# GFB_Basisstation.net
KiCad netlist of a schematic drawn in EAGLE
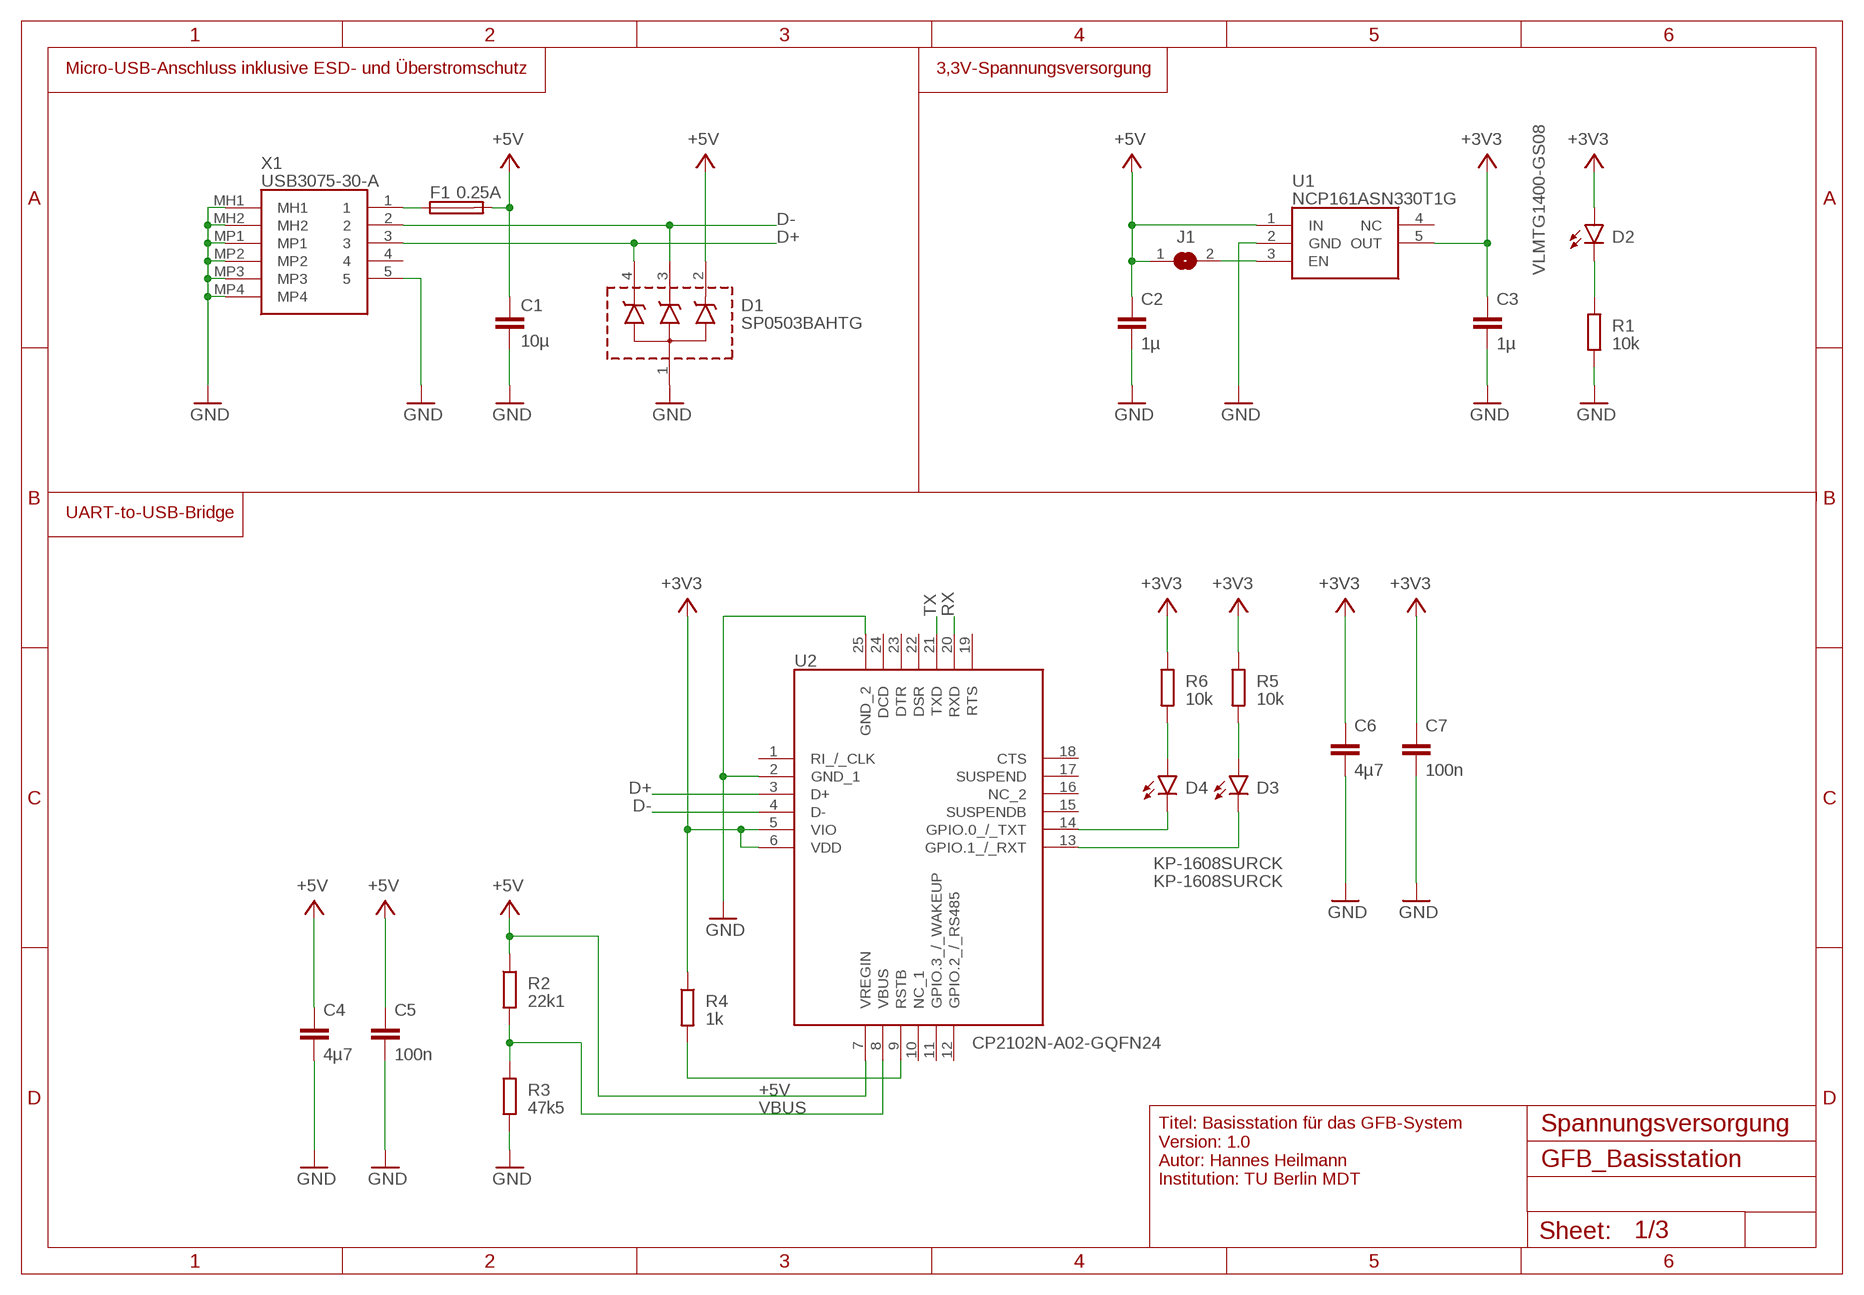
[diagram p0: schematic, sheet 1]
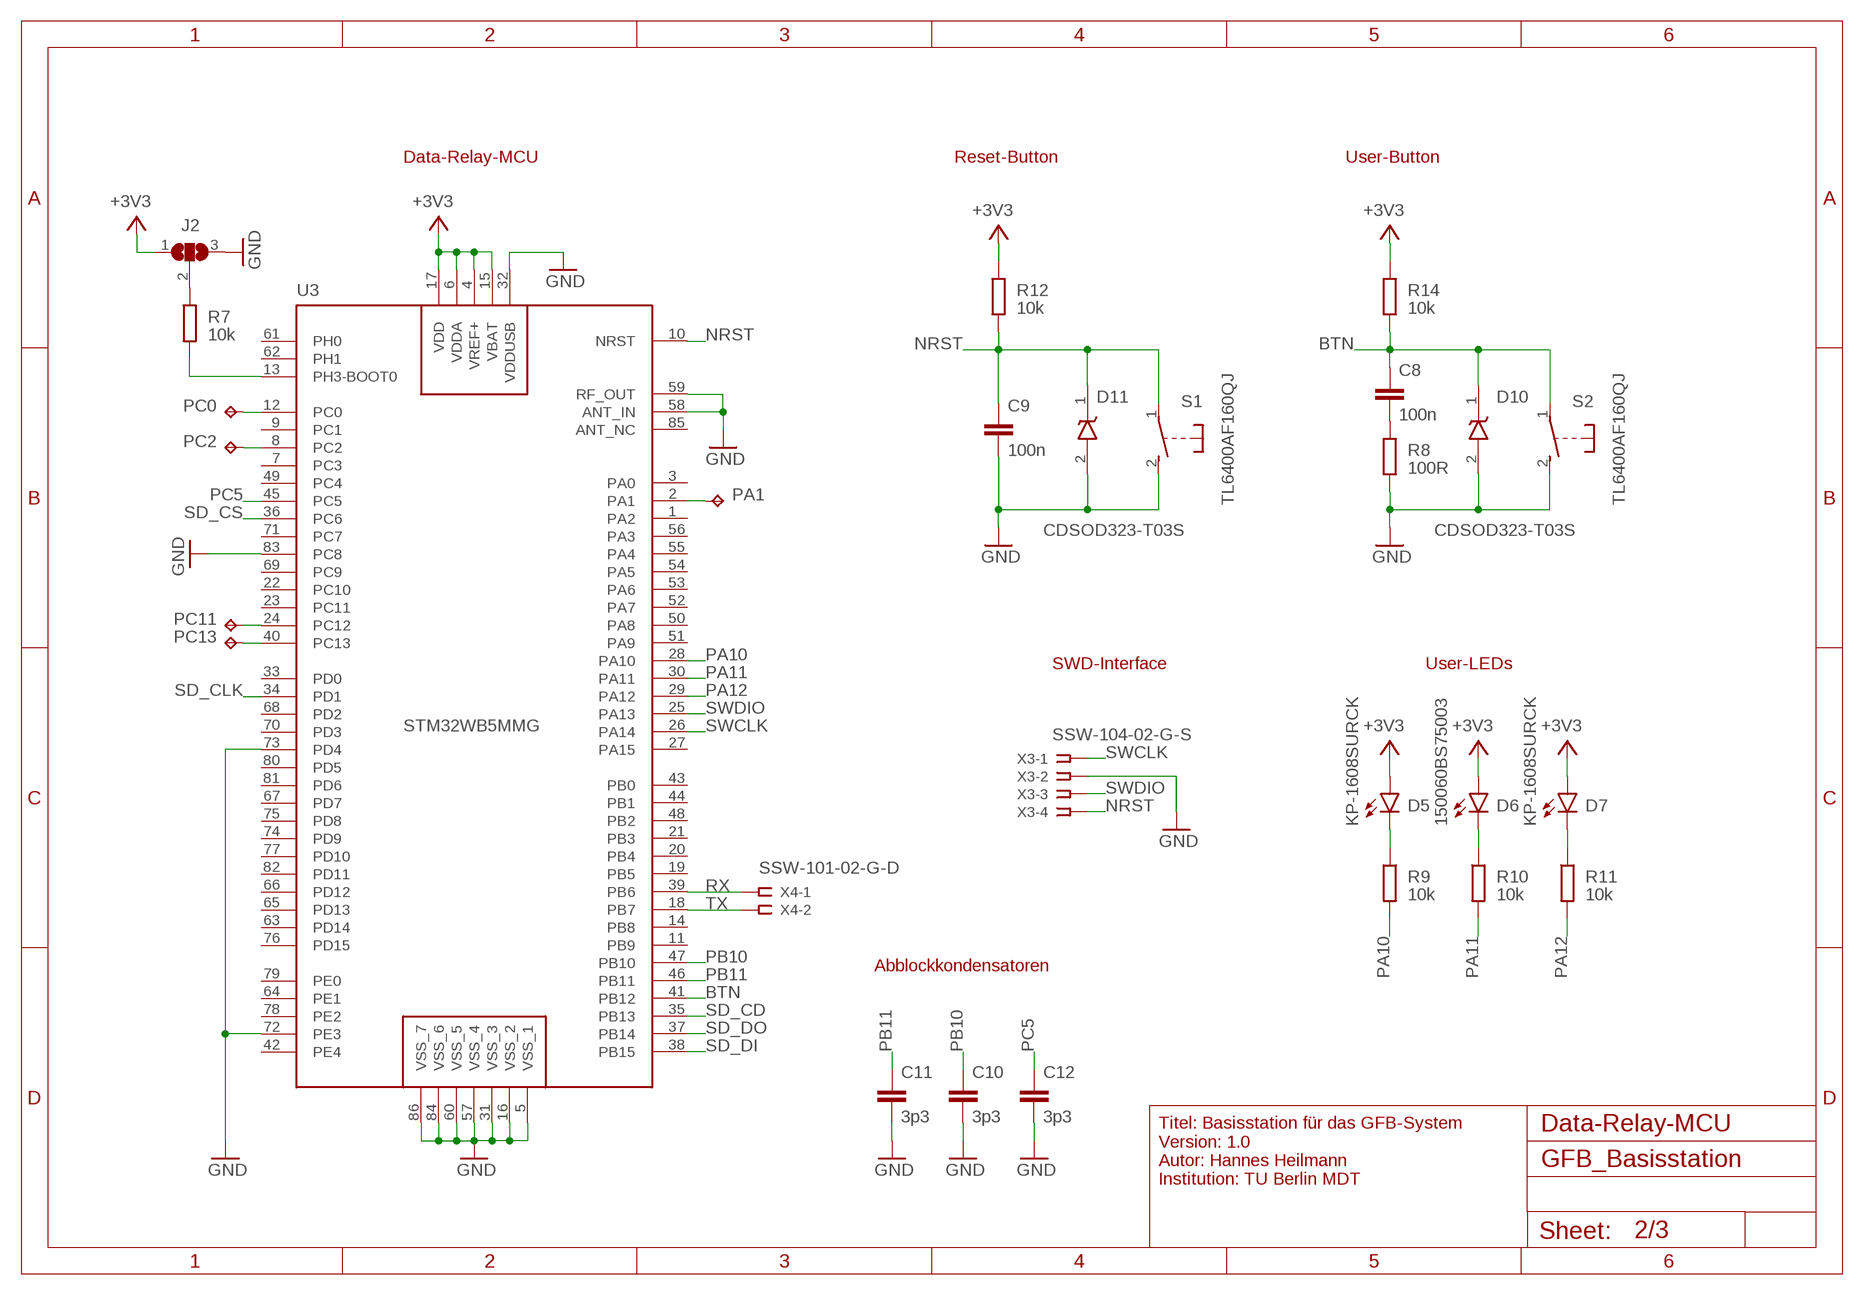
[diagram p1: schematic, sheet 2]
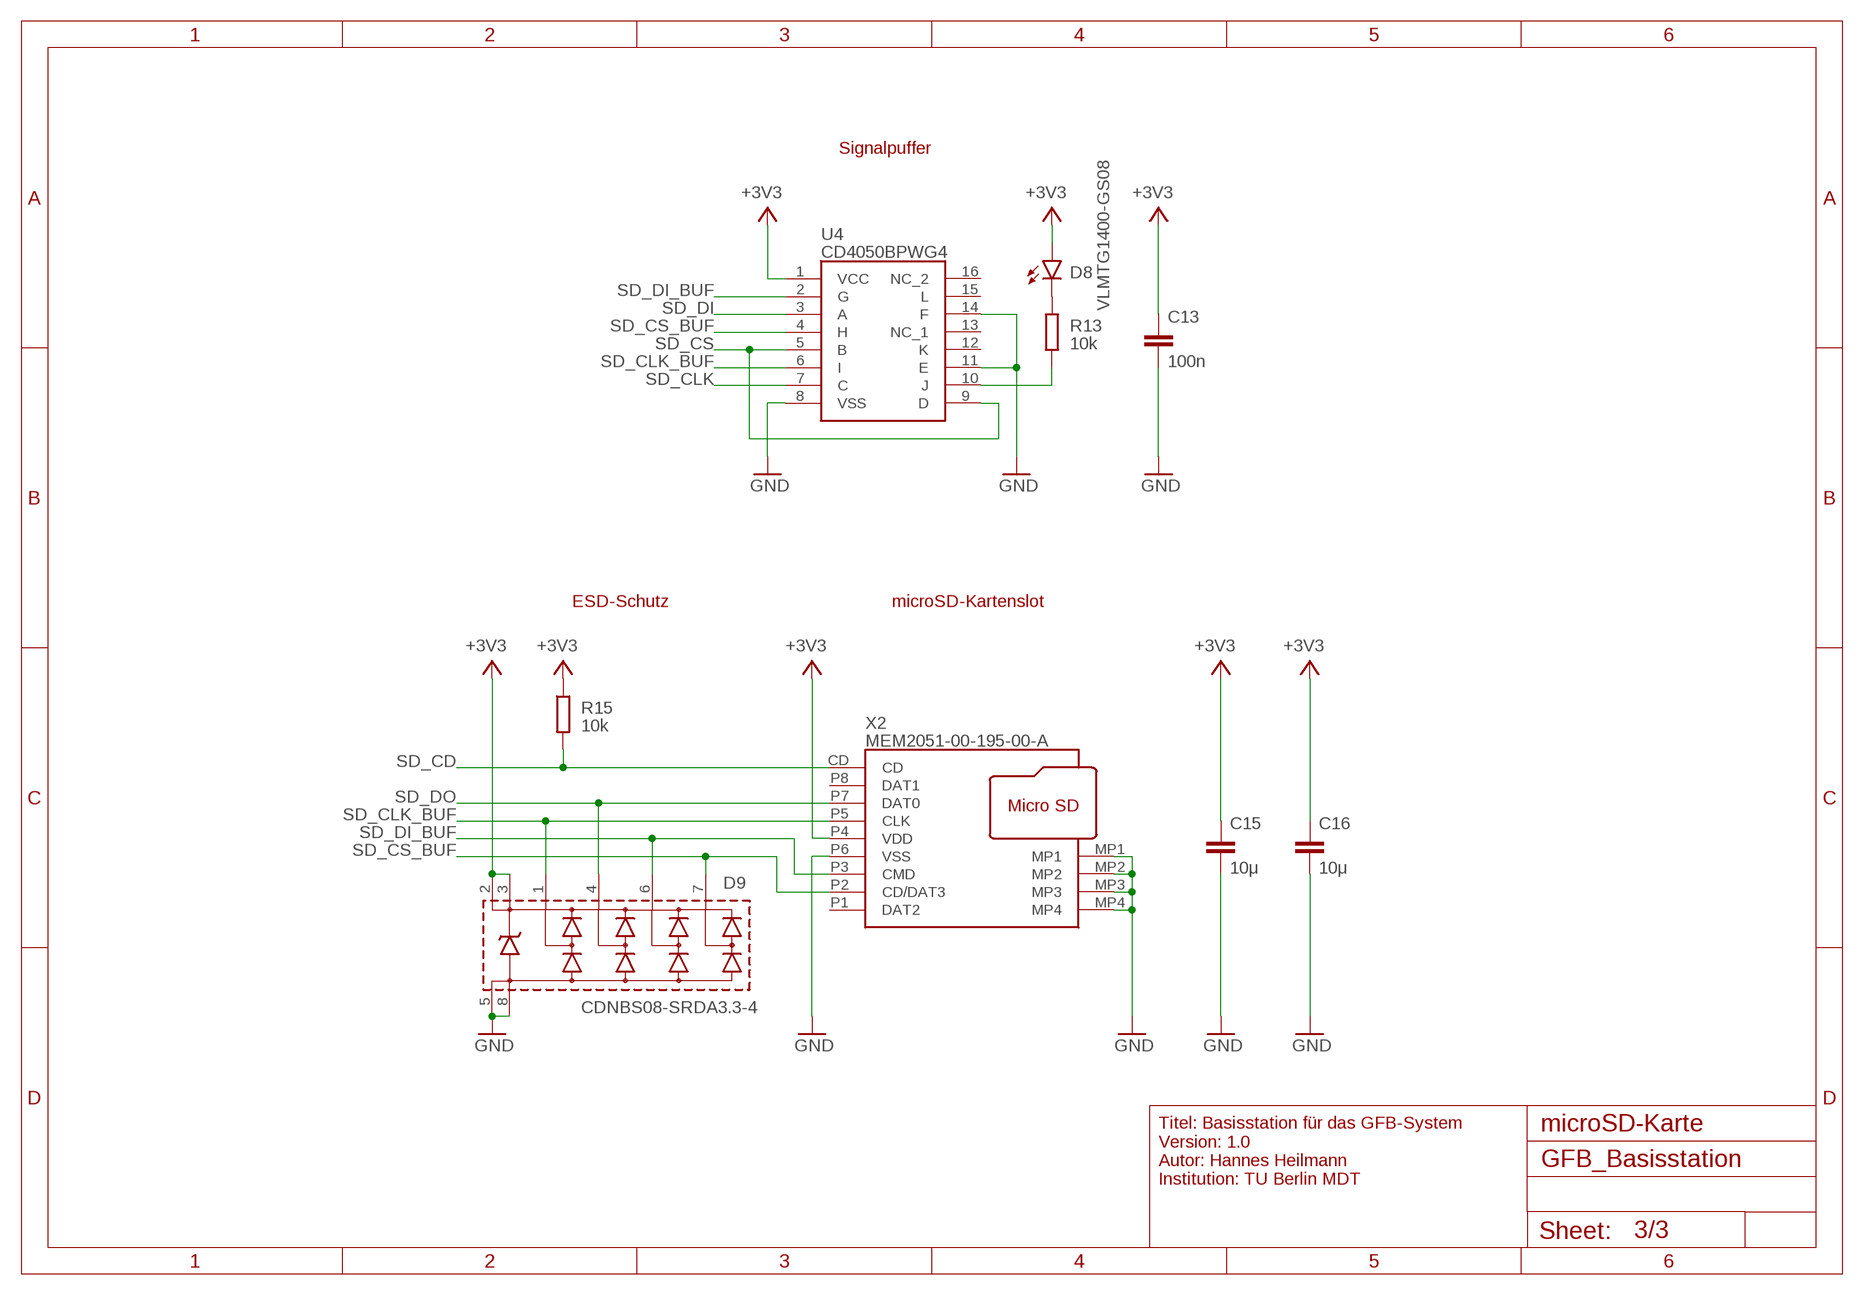
[diagram p2: schematic, sheet 3]

(export (version "E")
  (design (tool "Eeschema 10.0.6"))
  (components
    (comp (ref "C1")
      (value "10µ")
      (footprint "eagle-import:PATCHPOLYGRAPHV1_1608M")
      (libsource (lib "eagle-import") (part "C_OUTLINEC0603_OUTLINE"))
    )
    (comp (ref "C2")
      (value "1µ")
      (footprint "eagle-import:PATCHPOLYGRAPHV1_1608M")
      (libsource (lib "eagle-import") (part "C_OUTLINEC0603_OUTLINE"))
    )
    (comp (ref "C3")
      (value "1µ")
      (footprint "eagle-import:PATCHPOLYGRAPHV1_1608M")
      (libsource (lib "eagle-import") (part "C_OUTLINEC0603_OUTLINE"))
    )
    (comp (ref "C4")
      (value "4µ7")
      (footprint "eagle-import:PATCHPOLYGRAPHV1_1608M")
      (libsource (lib "eagle-import") (part "C_OUTLINEC0603_OUTLINE"))
    )
    (comp (ref "C5")
      (value "100n")
      (footprint "eagle-import:PATCHPOLYGRAPHV1_1608M")
      (libsource (lib "eagle-import") (part "C_OUTLINEC0603_OUTLINE"))
    )
    (comp (ref "C6")
      (value "4µ7")
      (footprint "eagle-import:PATCHPOLYGRAPHV1_1608M")
      (libsource (lib "eagle-import") (part "C_OUTLINEC0603_OUTLINE"))
    )
    (comp (ref "C7")
      (value "100n")
      (footprint "eagle-import:PATCHPOLYGRAPHV1_1608M")
      (libsource (lib "eagle-import") (part "C_OUTLINEC0603_OUTLINE"))
    )
    (comp (ref "D1")
      (value "SP0503BAHTG")
      (footprint "eagle-import:SP0503BAHTG")
      (fields (field (name "MOUSER_PART_NUMBER") "576-SP0503BAHTG"))
      (libsource (lib "eagle-import") (part "SP0503BAHTG"))
    )
    (comp (ref "D2")
      (value "VLMTG1400-GS08")
      (footprint "eagle-import:CHIPLED_0603")
      (libsource (lib "eagle-import") (part "LEDCHIPLED_0603"))
    )
    (comp (ref "D3")
      (value "KP-1608SURCK")
      (footprint "eagle-import:CHIPLED_0603")
      (libsource (lib "eagle-import") (part "LEDCHIPLED_0603"))
    )
    (comp (ref "D4")
      (value "KP-1608SURCK")
      (footprint "eagle-import:CHIPLED_0603")
      (libsource (lib "eagle-import") (part "LEDCHIPLED_0603"))
    )
    (comp (ref "F1")
      (value "SF-0603FP025F-2")
      (footprint "eagle-import:R0603")
      (libsource (lib "eagle-import") (part "SF-0603FP025F-2"))
    )
    (comp (ref "J1") (value "SJ") (footprint "eagle-import:SJ") (libsource (lib "eagle-import") (part "SJ")))
    (comp (ref "R1")
      (value "10k")
      (footprint "eagle-import:PATCHPOLYGRAPHV1_1608M")
      (libsource (lib "eagle-import") (part "R_OUTLINER0603_OUTLINE"))
    )
    (comp (ref "R2")
      (value "22k1")
      (footprint "eagle-import:PATCHPOLYGRAPHV1_1608M")
      (libsource (lib "eagle-import") (part "R_OUTLINER0603_OUTLINE"))
    )
    (comp (ref "R3")
      (value "47k5")
      (footprint "eagle-import:PATCHPOLYGRAPHV1_1608M")
      (libsource (lib "eagle-import") (part "R_OUTLINER0603_OUTLINE"))
    )
    (comp (ref "R4")
      (value "1k")
      (footprint "eagle-import:PATCHPOLYGRAPHV1_1608M")
      (libsource (lib "eagle-import") (part "R_OUTLINER0603_OUTLINE"))
    )
    (comp (ref "R5")
      (value "10k")
      (footprint "eagle-import:PATCHPOLYGRAPHV1_1608M")
      (libsource (lib "eagle-import") (part "R_OUTLINER0603_OUTLINE"))
    )
    (comp (ref "R6")
      (value "10k")
      (footprint "eagle-import:PATCHPOLYGRAPHV1_1608M")
      (libsource (lib "eagle-import") (part "R_OUTLINER0603_OUTLINE"))
    )
    (comp (ref "U1")
      (value "NCP161ASN330T1G")
      (footprint "eagle-import:SOT95P280X145-5N")
      (fields (field (name "MOUSER_PART_NUMBER") "863-NCP161ASN330T1G"))
      (libsource (lib "eagle-import") (part "NCP161ASN330T1G"))
    )
    (comp (ref "U2")
      (value "CP2102N-A02-GQFN24")
      (footprint "eagle-import:QFN50P400X400X80-25N")
      (fields (field (name "MOUSER_PART_NUMBER") "634-CP2102NA02GQFN24"))
      (libsource (lib "eagle-import") (part "CP2102N-A02-GQFN24"))
    )
    (comp (ref "X1")
      (value "USB3075-30-A")
      (footprint "eagle-import:USB307530A")
      (fields (field (name "MOUSER_PART_NUMBER") "640-USB3075-30-A"))
      (libsource (lib "eagle-import") (part "USB3075-30-A"))
    )
    (comp (ref "C8")
      (value "100n")
      (footprint "eagle-import:PATCHPOLYGRAPHV1_1608M")
      (libsource (lib "eagle-import") (part "C_OUTLINEC0603_OUTLINE"))
    )
    (comp (ref "C9")
      (value "100n")
      (footprint "eagle-import:PATCHPOLYGRAPHV1_1608M")
      (libsource (lib "eagle-import") (part "C_OUTLINEC0603_OUTLINE"))
    )
    (comp (ref "C10")
      (value "3p3")
      (footprint "eagle-import:PATCHPOLYGRAPHV1_1608M")
      (libsource (lib "eagle-import") (part "C_OUTLINEC0603_OUTLINE"))
    )
    (comp (ref "C11")
      (value "3p3")
      (footprint "eagle-import:PATCHPOLYGRAPHV1_1608M")
      (libsource (lib "eagle-import") (part "C_OUTLINEC0603_OUTLINE"))
    )
    (comp (ref "C12")
      (value "3p3")
      (footprint "eagle-import:PATCHPOLYGRAPHV1_1608M")
      (libsource (lib "eagle-import") (part "C_OUTLINEC0603_OUTLINE"))
    )
    (comp (ref "D5")
      (value "KP-1608SURCK")
      (footprint "eagle-import:CHIPLED_0603")
      (libsource (lib "eagle-import") (part "LEDCHIPLED_0603"))
    )
    (comp (ref "D6")
      (value "150060BS75003")
      (footprint "eagle-import:CHIPLED_0603")
      (libsource (lib "eagle-import") (part "LEDCHIPLED_0603"))
    )
    (comp (ref "D7")
      (value "KP-1608SURCK")
      (footprint "eagle-import:CHIPLED_0603")
      (libsource (lib "eagle-import") (part "LEDCHIPLED_0603"))
    )
    (comp (ref "D10")
      (value "CDSOD323-T03S")
      (footprint "eagle-import:SOD2513X114N")
      (fields (field (name "MOUSER_PART_NUMBER") "652-CDSOD323-T03S"))
      (libsource (lib "eagle-import") (part "CDSOD323-T03S"))
    )
    (comp (ref "D11")
      (value "CDSOD323-T03S")
      (footprint "eagle-import:SOD2513X114N")
      (fields (field (name "MOUSER_PART_NUMBER") "652-CDSOD323-T03S"))
      (libsource (lib "eagle-import") (part "CDSOD323-T03S"))
    )
    (comp (ref "J2")
      (value "JUMPER_3JUMPER_3_0603")
      (footprint "eagle-import:JUMPER_3_0603")
      (libsource (lib "eagle-import") (part "JUMPER_3JUMPER_3_0603"))
    )
    (comp (ref "PA1")
      (value "TPTP06R")
      (footprint "eagle-import:TP06R")
      (libsource (lib "eagle-import") (part "TPTP06R"))
    )
    (comp (ref "PC0")
      (value "TPTP06R")
      (footprint "eagle-import:TP06R")
      (libsource (lib "eagle-import") (part "TPTP06R"))
    )
    (comp (ref "PC2")
      (value "TPTP06R")
      (footprint "eagle-import:TP06R")
      (libsource (lib "eagle-import") (part "TPTP06R"))
    )
    (comp (ref "PC11")
      (value "TPTP06R")
      (footprint "eagle-import:TP06R")
      (libsource (lib "eagle-import") (part "TPTP06R"))
    )
    (comp (ref "PC13")
      (value "TPTP06R")
      (footprint "eagle-import:TP06R")
      (libsource (lib "eagle-import") (part "TPTP06R"))
    )
    (comp (ref "R7")
      (value "10k")
      (footprint "eagle-import:PATCHPOLYGRAPHV1_1608M")
      (libsource (lib "eagle-import") (part "R_OUTLINER0603_OUTLINE"))
    )
    (comp (ref "R8")
      (value "100R")
      (footprint "eagle-import:PATCHPOLYGRAPHV1_1608M")
      (libsource (lib "eagle-import") (part "R_OUTLINER0603_OUTLINE"))
    )
    (comp (ref "R9")
      (value "10k")
      (footprint "eagle-import:PATCHPOLYGRAPHV1_1608M")
      (libsource (lib "eagle-import") (part "R_OUTLINER0603_OUTLINE"))
    )
    (comp (ref "R10")
      (value "10k")
      (footprint "eagle-import:PATCHPOLYGRAPHV1_1608M")
      (libsource (lib "eagle-import") (part "R_OUTLINER0603_OUTLINE"))
    )
    (comp (ref "R11")
      (value "10k")
      (footprint "eagle-import:PATCHPOLYGRAPHV1_1608M")
      (libsource (lib "eagle-import") (part "R_OUTLINER0603_OUTLINE"))
    )
    (comp (ref "R12")
      (value "10k")
      (footprint "eagle-import:PATCHPOLYGRAPHV1_1608M")
      (libsource (lib "eagle-import") (part "R_OUTLINER0603_OUTLINE"))
    )
    (comp (ref "R14")
      (value "10k")
      (footprint "eagle-import:PATCHPOLYGRAPHV1_1608M")
      (libsource (lib "eagle-import") (part "R_OUTLINER0603_OUTLINE"))
    )
    (comp (ref "S1")
      (value "TL6400AF160QJ")
      (footprint "eagle-import:TL6400AF160QJ")
      (fields (field (name "MOUSER_PART_NUMBER") "612-TL6400AF160QJ"))
      (libsource (lib "eagle-import") (part "TL6400AF160QJ"))
    )
    (comp (ref "S2")
      (value "TL6400AF160QJ")
      (footprint "eagle-import:TL6400AF160QJ")
      (fields (field (name "MOUSER_PART_NUMBER") "612-TL6400AF160QJ"))
      (libsource (lib "eagle-import") (part "TL6400AF160QJ"))
    )
    (comp (ref "U3")
      (value "STM32WB5MMG")
      (footprint "eagle-import:STM32WB5MMG")
      (libsource (lib "eagle-import") (part "STM32WB5MMG"))
    )
    (comp (ref "X3")
      (value "SSW-104-02-G-S")
      (footprint "eagle-import:SSW-104-02-G-S")
      (fields (field (name "MF") "Samtec Inc."))
      (libsource (lib "eagle-import") (part "SSW-104-02-G-S"))
    )
    (comp (ref "X4")
      (value "SSW-101-02-G-D")
      (footprint "eagle-import:SSW-101-02-G-D")
      (fields (field (name "MF") "Samtec Inc."))
      (libsource (lib "eagle-import") (part "SSW-101-02-G-D"))
    )
    (comp (ref "C13")
      (value "100n")
      (footprint "eagle-import:PATCHPOLYGRAPHV1_1608M")
      (libsource (lib "eagle-import") (part "C_OUTLINEC0603_OUTLINE"))
    )
    (comp (ref "C15")
      (value "10μ")
      (footprint "eagle-import:PATCHPOLYGRAPHV1_1608M")
      (libsource (lib "eagle-import") (part "C_OUTLINEC0603_OUTLINE"))
    )
    (comp (ref "C16")
      (value "10μ")
      (footprint "eagle-import:PATCHPOLYGRAPHV1_1608M")
      (libsource (lib "eagle-import") (part "C_OUTLINEC0603_OUTLINE"))
    )
    (comp (ref "D8")
      (value "VLMTG1400-GS08")
      (footprint "eagle-import:CHIPLED_0603")
      (libsource (lib "eagle-import") (part "LEDCHIPLED_0603"))
    )
    (comp (ref "D9")
      (value "CDNBS08-SRDA3.3-4")
      (footprint "eagle-import:SOIC127P600X175-8N")
      (fields (field (name "MOUSER_PART_NUMBER") "652-CDNBS08SRDA3.3-4"))
      (libsource (lib "eagle-import") (part "CDNBS08-SRDA3.3-4"))
    )
    (comp (ref "R13")
      (value "10k")
      (footprint "eagle-import:PATCHPOLYGRAPHV1_1608M")
      (libsource (lib "eagle-import") (part "R_OUTLINER0603_OUTLINE"))
    )
    (comp (ref "R15")
      (value "10k")
      (footprint "eagle-import:PATCHPOLYGRAPHV1_1608M")
      (libsource (lib "eagle-import") (part "R_OUTLINER0603_OUTLINE"))
    )
    (comp (ref "U4")
      (value "CD4050BPWG4")
      (footprint "eagle-import:SOP65P640X120-16N")
      (fields (field (name "MOUSER_PART_NUMBER") "595-CD4050BPWG4"))
      (libsource (lib "eagle-import") (part "CD4050BPWG4"))
    )
    (comp (ref "X2")
      (value "MEM2051-00-195-00-A")
      (footprint "eagle-import:MEM20510019500A")
      (fields (field (name "MOUSER_PART_NUMBER") "640-MEM20510019500A"))
      (libsource (lib "eagle-import") (part "MEM2051-00-195-00-A"))
    )
  )
  (nets
    (net (code "1") (name "+3V3") (class "Default")
      (node (ref "C13") (pin "1") (pinfunction "1_1") (pintype "passive"))
      (node (ref "C15") (pin "1") (pinfunction "1_1") (pintype "passive"))
      (node (ref "C16") (pin "1") (pinfunction "1_1") (pintype "passive"))
      (node (ref "C3") (pin "1") (pinfunction "1_1") (pintype "passive"))
      (node (ref "C6") (pin "1") (pinfunction "1_1") (pintype "passive"))
      (node (ref "C7") (pin "1") (pinfunction "1_1") (pintype "passive"))
      (node (ref "D2") (pin "A") (pinfunction "A_A") (pintype "passive"))
      (node (ref "D5") (pin "A") (pinfunction "A_A") (pintype "passive"))
      (node (ref "D6") (pin "A") (pinfunction "A_A") (pintype "passive"))
      (node (ref "D7") (pin "A") (pinfunction "A_A") (pintype "passive"))
      (node (ref "D8") (pin "A") (pinfunction "A_A") (pintype "passive"))
      (node (ref "D9") (pin "2") (pinfunction "+VREF_1_2") (pintype "bidirectional"))
      (node (ref "D9") (pin "3") (pinfunction "+VREF_2_3") (pintype "bidirectional"))
      (node (ref "J2") (pin "1") (pinfunction "1_1") (pintype "passive"))
      (node (ref "R12") (pin "1") (pinfunction "1_1") (pintype "passive"))
      (node (ref "R14") (pin "1") (pinfunction "1_1") (pintype "passive"))
      (node (ref "R15") (pin "1") (pinfunction "1_1") (pintype "passive"))
      (node (ref "R4") (pin "1") (pinfunction "1_1") (pintype "passive"))
      (node (ref "R5") (pin "1") (pinfunction "1_1") (pintype "passive"))
      (node (ref "R6") (pin "1") (pinfunction "1_1") (pintype "passive"))
      (node (ref "U1") (pin "5") (pinfunction "OUT_5") (pintype "bidirectional"))
      (node (ref "U2") (pin "5") (pinfunction "VIO_5") (pintype "bidirectional"))
      (node (ref "U2") (pin "6") (pinfunction "VDD_6") (pintype "bidirectional"))
      (node (ref "U3") (pin "15") (pinfunction "VBAT_15") (pintype "bidirectional"))
      (node (ref "U3") (pin "17") (pinfunction "VDD_17") (pintype "bidirectional"))
      (node (ref "U3") (pin "4") (pinfunction "VREF+_4") (pintype "bidirectional"))
      (node (ref "U3") (pin "6") (pinfunction "VDDA_6") (pintype "bidirectional"))
      (node (ref "U4") (pin "1") (pinfunction "VCC_1") (pintype "bidirectional"))
      (node (ref "X2") (pin "P4") (pinfunction "VDD_P4") (pintype "bidirectional"))
    )
    (net (code "2") (name "+5V") (class "Default")
      (node (ref "C1") (pin "1") (pinfunction "1_1") (pintype "passive"))
      (node (ref "C2") (pin "1") (pinfunction "1_1") (pintype "passive"))
      (node (ref "C4") (pin "1") (pinfunction "1_1") (pintype "passive"))
      (node (ref "C5") (pin "1") (pinfunction "1_1") (pintype "passive"))
      (node (ref "D1") (pin "2") (pinfunction "K_1_2") (pintype "bidirectional"))
      (node (ref "F1") (pin "2") (pinfunction "2_2") (pintype "passive"))
      (node (ref "J1") (pin "1") (pinfunction "1_1") (pintype "passive"))
      (node (ref "R2") (pin "1") (pinfunction "1_1") (pintype "passive"))
      (node (ref "U1") (pin "1") (pinfunction "IN_1") (pintype "bidirectional"))
      (node (ref "U2") (pin "7") (pinfunction "VREGIN_7") (pintype "bidirectional"))
    )
    (net (code "3") (name "BTN") (class "Default")
      (node (ref "C8") (pin "1") (pinfunction "1_1") (pintype "passive"))
      (node (ref "D10") (pin "1") (pinfunction "K_1") (pintype "bidirectional"))
      (node (ref "R14") (pin "2") (pinfunction "2_2") (pintype "passive"))
      (node (ref "S2") (pin "1") (pinfunction "P_1") (pintype "passive"))
      (node (ref "U3") (pin "41") (pinfunction "PB12_41") (pintype "bidirectional"))
    )
    (net (code "4") (name "D+") (class "Default")
      (node (ref "D1") (pin "4") (pinfunction "K_3_4") (pintype "bidirectional"))
      (node (ref "U2") (pin "3") (pinfunction "D+_3") (pintype "bidirectional"))
      (node (ref "X1") (pin "3") (pinfunction "3_3") (pintype "bidirectional"))
    )
    (net (code "5") (name "D-") (class "Default")
      (node (ref "D1") (pin "3") (pinfunction "K_2_3") (pintype "bidirectional"))
      (node (ref "U2") (pin "4") (pinfunction "D-_4") (pintype "bidirectional"))
      (node (ref "X1") (pin "2") (pinfunction "2_2") (pintype "bidirectional"))
    )
    (net (code "6") (name "GND") (class "Default")
      (node (ref "C1") (pin "2") (pinfunction "2_2") (pintype "passive"))
      (node (ref "C10") (pin "2") (pinfunction "2_2") (pintype "passive"))
      (node (ref "C11") (pin "2") (pinfunction "2_2") (pintype "passive"))
      (node (ref "C12") (pin "2") (pinfunction "2_2") (pintype "passive"))
      (node (ref "C13") (pin "2") (pinfunction "2_2") (pintype "passive"))
      (node (ref "C15") (pin "2") (pinfunction "2_2") (pintype "passive"))
      (node (ref "C16") (pin "2") (pinfunction "2_2") (pintype "passive"))
      (node (ref "C2") (pin "2") (pinfunction "2_2") (pintype "passive"))
      (node (ref "C3") (pin "2") (pinfunction "2_2") (pintype "passive"))
      (node (ref "C4") (pin "2") (pinfunction "2_2") (pintype "passive"))
      (node (ref "C5") (pin "2") (pinfunction "2_2") (pintype "passive"))
      (node (ref "C6") (pin "2") (pinfunction "2_2") (pintype "passive"))
      (node (ref "C7") (pin "2") (pinfunction "2_2") (pintype "passive"))
      (node (ref "C9") (pin "2") (pinfunction "2_2") (pintype "passive"))
      (node (ref "D1") (pin "1") (pinfunction "COMMON_A_1") (pintype "bidirectional"))
      (node (ref "D10") (pin "2") (pinfunction "A_2") (pintype "bidirectional"))
      (node (ref "D11") (pin "2") (pinfunction "A_2") (pintype "bidirectional"))
      (node (ref "D9") (pin "5") (pinfunction "GND_1_5") (pintype "bidirectional"))
      (node (ref "D9") (pin "8") (pinfunction "GND_2_8") (pintype "bidirectional"))
      (node (ref "J2") (pin "3") (pinfunction "3_3") (pintype "passive"))
      (node (ref "R1") (pin "2") (pinfunction "2_2") (pintype "passive"))
      (node (ref "R3") (pin "2") (pinfunction "2_2") (pintype "passive"))
      (node (ref "R8") (pin "2") (pinfunction "2_2") (pintype "passive"))
      (node (ref "S1") (pin "2") (pinfunction "S_2") (pintype "passive"))
      (node (ref "S2") (pin "2") (pinfunction "S_2") (pintype "passive"))
      (node (ref "U1") (pin "2") (pinfunction "GND_2") (pintype "power_in"))
      (node (ref "U2") (pin "2") (pinfunction "GND_1_2") (pintype "bidirectional"))
      (node (ref "U2") (pin "25") (pinfunction "GND_2_25") (pintype "bidirectional"))
      (node (ref "U3") (pin "16") (pinfunction "VSS_2_16") (pintype "bidirectional"))
      (node (ref "U3") (pin "31") (pinfunction "VSS_3_31") (pintype "bidirectional"))
      (node (ref "U3") (pin "32") (pinfunction "VDDUSB_32") (pintype "bidirectional"))
      (node (ref "U3") (pin "5") (pinfunction "VSS_1_5") (pintype "bidirectional"))
      (node (ref "U3") (pin "57") (pinfunction "VSS_4_57") (pintype "bidirectional"))
      (node (ref "U3") (pin "58") (pinfunction "ANT_IN_58") (pintype "bidirectional"))
      (node (ref "U3") (pin "59") (pinfunction "RF_OUT_59") (pintype "bidirectional"))
      (node (ref "U3") (pin "60") (pinfunction "VSS_5_60") (pintype "bidirectional"))
      (node (ref "U3") (pin "72") (pinfunction "PE3_72") (pintype "bidirectional"))
      (node (ref "U3") (pin "73") (pinfunction "PD4_73") (pintype "bidirectional"))
      (node (ref "U3") (pin "83") (pinfunction "PC8_83") (pintype "bidirectional"))
      (node (ref "U3") (pin "84") (pinfunction "VSS_6_84") (pintype "bidirectional"))
      (node (ref "U3") (pin "86") (pinfunction "VSS_7_86") (pintype "bidirectional"))
      (node (ref "U4") (pin "11") (pinfunction "E_11") (pintype "bidirectional"))
      (node (ref "U4") (pin "14") (pinfunction "F_14") (pintype "bidirectional"))
      (node (ref "U4") (pin "8") (pinfunction "VSS_8") (pintype "bidirectional"))
      (node (ref "X1") (pin "5") (pinfunction "5_5") (pintype "bidirectional"))
      (node (ref "X1") (pin "MH1") (pinfunction "MH1_MH1") (pintype "bidirectional"))
      (node (ref "X1") (pin "MH2") (pinfunction "MH2_MH2") (pintype "bidirectional"))
      (node (ref "X1") (pin "MP1") (pinfunction "MP1_MP1") (pintype "bidirectional"))
      (node (ref "X1") (pin "MP2") (pinfunction "MP2_MP2") (pintype "bidirectional"))
      (node (ref "X1") (pin "MP3") (pinfunction "MP3_MP3") (pintype "bidirectional"))
      (node (ref "X1") (pin "MP4") (pinfunction "MP4_MP4") (pintype "bidirectional"))
      (node (ref "X2") (pin "MP1") (pinfunction "MP1_MP1") (pintype "bidirectional"))
      (node (ref "X2") (pin "MP2") (pinfunction "MP2_MP2") (pintype "bidirectional"))
      (node (ref "X2") (pin "MP3") (pinfunction "MP3_MP3") (pintype "bidirectional"))
      (node (ref "X2") (pin "MP4") (pinfunction "MP4_MP4") (pintype "bidirectional"))
      (node (ref "X2") (pin "P6") (pinfunction "VSS_P6") (pintype "bidirectional"))
      (node (ref "X3") (pin "2") (pinfunction "1_2") (pintype "passive"))
    )
    (net (code "7") (name "NRST") (class "Default")
      (node (ref "C9") (pin "1") (pinfunction "1_1") (pintype "passive"))
      (node (ref "D11") (pin "1") (pinfunction "K_1") (pintype "bidirectional"))
      (node (ref "R12") (pin "2") (pinfunction "2_2") (pintype "passive"))
      (node (ref "S1") (pin "1") (pinfunction "P_1") (pintype "passive"))
      (node (ref "U3") (pin "10") (pinfunction "NRST_10") (pintype "bidirectional"))
      (node (ref "X3") (pin "4") (pinfunction "1_4") (pintype "passive"))
    )
    (net (code "8") (name "Net-(C8-Pad2)") (class "Default")
      (node (ref "C8") (pin "2") (pinfunction "2_2") (pintype "passive"))
      (node (ref "R8") (pin "1") (pinfunction "1_1") (pintype "passive"))
    )
    (net (code "9") (name "Net-(D2-PadC)") (class "Default")
      (node (ref "D2") (pin "C") (pinfunction "C_C") (pintype "passive"))
      (node (ref "R1") (pin "1") (pinfunction "1_1") (pintype "passive"))
    )
    (net (code "10") (name "Net-(D3-PadA)") (class "Default")
      (node (ref "D3") (pin "A") (pinfunction "A_A") (pintype "passive"))
      (node (ref "R5") (pin "2") (pinfunction "2_2") (pintype "passive"))
    )
    (net (code "11") (name "Net-(D4-PadA)") (class "Default")
      (node (ref "D4") (pin "A") (pinfunction "A_A") (pintype "passive"))
      (node (ref "R6") (pin "2") (pinfunction "2_2") (pintype "passive"))
    )
    (net (code "12") (name "Net-(D5-PadC)") (class "Default")
      (node (ref "D5") (pin "C") (pinfunction "C_C") (pintype "passive"))
      (node (ref "R9") (pin "1") (pinfunction "1_1") (pintype "passive"))
    )
    (net (code "13") (name "Net-(D6-PadC)") (class "Default")
      (node (ref "D6") (pin "C") (pinfunction "C_C") (pintype "passive"))
      (node (ref "R10") (pin "1") (pinfunction "1_1") (pintype "passive"))
    )
    (net (code "14") (name "Net-(D7-PadC)") (class "Default")
      (node (ref "D7") (pin "C") (pinfunction "C_C") (pintype "passive"))
      (node (ref "R11") (pin "1") (pinfunction "1_1") (pintype "passive"))
    )
    (net (code "15") (name "Net-(D8-PadC)") (class "Default")
      (node (ref "D8") (pin "C") (pinfunction "C_C") (pintype "passive"))
      (node (ref "R13") (pin "1") (pinfunction "1_1") (pintype "passive"))
    )
    (net (code "16") (name "Net-(F1-Pad1)") (class "Default")
      (node (ref "F1") (pin "1") (pinfunction "1_1") (pintype "passive"))
      (node (ref "X1") (pin "1") (pinfunction "1_1") (pintype "bidirectional"))
    )
    (net (code "17") (name "Net-(J2-Pad2)") (class "Default")
      (node (ref "J2") (pin "2") (pinfunction "2_2") (pintype "passive"))
      (node (ref "R7") (pin "1") (pinfunction "1_1") (pintype "passive"))
    )
    (net (code "18") (name "Net-(U1-EN)") (class "Default")
      (node (ref "J1") (pin "2") (pinfunction "2_2") (pintype "passive"))
      (node (ref "U1") (pin "3") (pinfunction "EN_3") (pintype "bidirectional"))
    )
    (net (code "19") (name "Net-(U2-GPIO.0_{slash}_TXT)") (class "Default")
      (node (ref "D4") (pin "C") (pinfunction "C_C") (pintype "passive"))
      (node (ref "U2") (pin "14") (pinfunction "GPIO.0_/_TXT_14") (pintype "bidirectional"))
    )
    (net (code "20") (name "Net-(U2-GPIO.1_{slash}_RXT)") (class "Default")
      (node (ref "D3") (pin "C") (pinfunction "C_C") (pintype "passive"))
      (node (ref "U2") (pin "13") (pinfunction "GPIO.1_/_RXT_13") (pintype "bidirectional"))
    )
    (net (code "21") (name "Net-(U2-RSTB)") (class "Default")
      (node (ref "R4") (pin "2") (pinfunction "2_2") (pintype "passive"))
      (node (ref "U2") (pin "9") (pinfunction "RSTB_9") (pintype "bidirectional"))
    )
    (net (code "22") (name "Net-(U3-PA1)") (class "Default")
      (node (ref "PA1") (pin "TP") (pinfunction "TP_TP") (pintype "input"))
      (node (ref "U3") (pin "2") (pinfunction "PA1_2") (pintype "bidirectional"))
    )
    (net (code "23") (name "Net-(U3-PC0)") (class "Default")
      (node (ref "PC0") (pin "TP") (pinfunction "TP_TP") (pintype "input"))
      (node (ref "U3") (pin "12") (pinfunction "PC0_12") (pintype "bidirectional"))
    )
    (net (code "24") (name "Net-(U3-PC2)") (class "Default")
      (node (ref "PC2") (pin "TP") (pinfunction "TP_TP") (pintype "input"))
      (node (ref "U3") (pin "8") (pinfunction "PC2_8") (pintype "bidirectional"))
    )
    (net (code "25") (name "Net-(U3-PC12)") (class "Default")
      (node (ref "PC11") (pin "TP") (pinfunction "TP_TP") (pintype "input"))
      (node (ref "U3") (pin "24") (pinfunction "PC12_24") (pintype "bidirectional"))
    )
    (net (code "26") (name "Net-(U3-PC13)") (class "Default")
      (node (ref "PC13") (pin "TP") (pinfunction "TP_TP") (pintype "input"))
      (node (ref "U3") (pin "40") (pinfunction "PC13_40") (pintype "bidirectional"))
    )
    (net (code "27") (name "Net-(U3-PH3-BOOT0)") (class "Default")
      (node (ref "R7") (pin "2") (pinfunction "2_2") (pintype "passive"))
      (node (ref "U3") (pin "13") (pinfunction "PH3-BOOT0_13") (pintype "bidirectional"))
    )
    (net (code "28") (name "Net-(U4-J)") (class "Default")
      (node (ref "R13") (pin "2") (pinfunction "2_2") (pintype "passive"))
      (node (ref "U4") (pin "10") (pinfunction "J_10") (pintype "bidirectional"))
    )
    (net (code "29") (name "PA10") (class "Default")
      (node (ref "R9") (pin "2") (pinfunction "2_2") (pintype "passive"))
      (node (ref "U3") (pin "28") (pinfunction "PA10_28") (pintype "bidirectional"))
    )
    (net (code "30") (name "PA11") (class "Default")
      (node (ref "R10") (pin "2") (pinfunction "2_2") (pintype "passive"))
      (node (ref "U3") (pin "30") (pinfunction "PA11_30") (pintype "bidirectional"))
    )
    (net (code "31") (name "PA12") (class "Default")
      (node (ref "R11") (pin "2") (pinfunction "2_2") (pintype "passive"))
      (node (ref "U3") (pin "29") (pinfunction "PA12_29") (pintype "bidirectional"))
    )
    (net (code "32") (name "PB10") (class "Default")
      (node (ref "C10") (pin "1") (pinfunction "1_1") (pintype "passive"))
      (node (ref "U3") (pin "47") (pinfunction "PB10_47") (pintype "bidirectional"))
    )
    (net (code "33") (name "PB11") (class "Default")
      (node (ref "C11") (pin "1") (pinfunction "1_1") (pintype "passive"))
      (node (ref "U3") (pin "46") (pinfunction "PB11_46") (pintype "bidirectional"))
    )
    (net (code "34") (name "PC5") (class "Default")
      (node (ref "C12") (pin "1") (pinfunction "1_1") (pintype "passive"))
      (node (ref "U3") (pin "45") (pinfunction "PC5_45") (pintype "bidirectional"))
    )
    (net (code "35") (name "RX") (class "Default")
      (node (ref "U2") (pin "20") (pinfunction "RXD_20") (pintype "bidirectional"))
      (node (ref "U3") (pin "39") (pinfunction "PB6_39") (pintype "bidirectional"))
      (node (ref "X4") (pin "1") (pinfunction "1_1") (pintype "passive"))
    )
    (net (code "36") (name "SD_CD") (class "Default")
      (node (ref "R15") (pin "2") (pinfunction "2_2") (pintype "passive"))
      (node (ref "U3") (pin "35") (pinfunction "PB13_35") (pintype "bidirectional"))
      (node (ref "X2") (pin "CD") (pinfunction "CD_CD") (pintype "bidirectional"))
    )
    (net (code "37") (name "SD_CLK") (class "Default")
      (node (ref "U3") (pin "34") (pinfunction "PD1_34") (pintype "bidirectional"))
      (node (ref "U4") (pin "7") (pinfunction "C_7") (pintype "bidirectional"))
    )
    (net (code "38") (name "SD_CLK_BUF") (class "Default")
      (node (ref "D9") (pin "1") (pinfunction "I/O_1_1") (pintype "bidirectional"))
      (node (ref "U4") (pin "6") (pinfunction "I_6") (pintype "bidirectional"))
      (node (ref "X2") (pin "P5") (pinfunction "CLK_P5") (pintype "bidirectional"))
    )
    (net (code "39") (name "SD_CS") (class "Default")
      (node (ref "U3") (pin "36") (pinfunction "PC6_36") (pintype "bidirectional"))
      (node (ref "U4") (pin "5") (pinfunction "B_5") (pintype "bidirectional"))
      (node (ref "U4") (pin "9") (pinfunction "D_9") (pintype "bidirectional"))
    )
    (net (code "40") (name "SD_CS_BUF") (class "Default")
      (node (ref "D9") (pin "7") (pinfunction "I/O_4_7") (pintype "bidirectional"))
      (node (ref "U4") (pin "4") (pinfunction "H_4") (pintype "bidirectional"))
      (node (ref "X2") (pin "P2") (pinfunction "CD/DAT3_P2") (pintype "bidirectional"))
    )
    (net (code "41") (name "SD_DI") (class "Default")
      (node (ref "U3") (pin "38") (pinfunction "PB15_38") (pintype "bidirectional"))
      (node (ref "U4") (pin "3") (pinfunction "A_3") (pintype "bidirectional"))
    )
    (net (code "42") (name "SD_DI_BUF") (class "Default")
      (node (ref "D9") (pin "6") (pinfunction "I/O_3_6") (pintype "bidirectional"))
      (node (ref "U4") (pin "2") (pinfunction "G_2") (pintype "bidirectional"))
      (node (ref "X2") (pin "P3") (pinfunction "CMD_P3") (pintype "bidirectional"))
    )
    (net (code "43") (name "SD_DO") (class "Default")
      (node (ref "D9") (pin "4") (pinfunction "I/O_2_4") (pintype "bidirectional"))
      (node (ref "U3") (pin "37") (pinfunction "PB14_37") (pintype "bidirectional"))
      (node (ref "X2") (pin "P7") (pinfunction "DAT0_P7") (pintype "bidirectional"))
    )
    (net (code "44") (name "SWCLK") (class "Default")
      (node (ref "U3") (pin "26") (pinfunction "PA14_26") (pintype "bidirectional"))
      (node (ref "X3") (pin "1") (pinfunction "1_1") (pintype "passive"))
    )
    (net (code "45") (name "SWDIO") (class "Default")
      (node (ref "U3") (pin "25") (pinfunction "PA13_25") (pintype "bidirectional"))
      (node (ref "X3") (pin "3") (pinfunction "1_3") (pintype "passive"))
    )
    (net (code "46") (name "TX") (class "Default")
      (node (ref "U2") (pin "21") (pinfunction "TXD_21") (pintype "bidirectional"))
      (node (ref "U3") (pin "18") (pinfunction "PB7_18") (pintype "bidirectional"))
      (node (ref "X4") (pin "2") (pinfunction "1_2") (pintype "passive"))
    )
    (net (code "47") (name "VBUS") (class "Default")
      (node (ref "R2") (pin "2") (pinfunction "2_2") (pintype "passive"))
      (node (ref "R3") (pin "1") (pinfunction "1_1") (pintype "passive"))
      (node (ref "U2") (pin "8") (pinfunction "VBUS_8") (pintype "bidirectional"))
    )
    (net (code "48") (name "unconnected-(U1-NC-Pad4)") (class "Default")
      (node (ref "U1") (pin "4") (pinfunction "NC_4") (pintype "no_connect"))
    )
    (net (code "49") (name "unconnected-(U2-CTS-Pad18)") (class "Default")
      (node (ref "U2") (pin "18") (pinfunction "CTS_18") (pintype "bidirectional"))
    )
    (net (code "50") (name "unconnected-(U2-DCD-Pad24)") (class "Default")
      (node (ref "U2") (pin "24") (pinfunction "DCD_24") (pintype "bidirectional"))
    )
    (net (code "51") (name "unconnected-(U2-DSR-Pad22)") (class "Default")
      (node (ref "U2") (pin "22") (pinfunction "DSR_22") (pintype "bidirectional"))
    )
    (net (code "52") (name "unconnected-(U2-DTR-Pad23)") (class "Default")
      (node (ref "U2") (pin "23") (pinfunction "DTR_23") (pintype "bidirectional"))
    )
    (net (code "53") (name "unconnected-(U2-GPIO.2_{slash}_RS485-Pad12)") (class "Default")
      (node (ref "U2") (pin "12") (pinfunction "GPIO.2_/_RS485_12") (pintype "bidirectional"))
    )
    (net (code "54") (name "unconnected-(U2-GPIO.3_{slash}_WAKEUP-Pad11)") (class "Default")
      (node (ref "U2") (pin "11") (pinfunction "GPIO.3_/_WAKEUP_11") (pintype "bidirectional"))
    )
    (net (code "55") (name "unconnected-(U2-NC_1-Pad10)") (class "Default")
      (node (ref "U2") (pin "10") (pinfunction "NC_1_10") (pintype "bidirectional"))
    )
    (net (code "56") (name "unconnected-(U2-NC_2-Pad16)") (class "Default")
      (node (ref "U2") (pin "16") (pinfunction "NC_2_16") (pintype "bidirectional"))
    )
    (net (code "57") (name "unconnected-(U2-RI_{slash}_CLK-Pad1)") (class "Default")
      (node (ref "U2") (pin "1") (pinfunction "RI_/_CLK_1") (pintype "bidirectional"))
    )
    (net (code "58") (name "unconnected-(U2-RTS-Pad19)") (class "Default")
      (node (ref "U2") (pin "19") (pinfunction "RTS_19") (pintype "bidirectional"))
    )
    (net (code "59") (name "unconnected-(U2-SUSPEND-Pad17)") (class "Default")
      (node (ref "U2") (pin "17") (pinfunction "SUSPEND_17") (pintype "bidirectional"))
    )
    (net (code "60") (name "unconnected-(U2-SUSPENDB-Pad15)") (class "Default")
      (node (ref "U2") (pin "15") (pinfunction "SUSPENDB_15") (pintype "bidirectional"))
    )
    (net (code "61") (name "unconnected-(U3-ANT_NC-Pad85)") (class "Default")
      (node (ref "U3") (pin "85") (pinfunction "ANT_NC_85") (pintype "no_connect"))
    )
    (net (code "62") (name "unconnected-(U3-PA0-Pad3)") (class "Default")
      (node (ref "U3") (pin "3") (pinfunction "PA0_3") (pintype "bidirectional"))
    )
    (net (code "63") (name "unconnected-(U3-PA2-Pad1)") (class "Default")
      (node (ref "U3") (pin "1") (pinfunction "PA2_1") (pintype "bidirectional"))
    )
    (net (code "64") (name "unconnected-(U3-PA3-Pad56)") (class "Default")
      (node (ref "U3") (pin "56") (pinfunction "PA3_56") (pintype "bidirectional"))
    )
    (net (code "65") (name "unconnected-(U3-PA4-Pad55)") (class "Default")
      (node (ref "U3") (pin "55") (pinfunction "PA4_55") (pintype "bidirectional"))
    )
    (net (code "66") (name "unconnected-(U3-PA5-Pad54)") (class "Default")
      (node (ref "U3") (pin "54") (pinfunction "PA5_54") (pintype "bidirectional"))
    )
    (net (code "67") (name "unconnected-(U3-PA6-Pad53)") (class "Default")
      (node (ref "U3") (pin "53") (pinfunction "PA6_53") (pintype "bidirectional"))
    )
    (net (code "68") (name "unconnected-(U3-PA7-Pad52)") (class "Default")
      (node (ref "U3") (pin "52") (pinfunction "PA7_52") (pintype "bidirectional"))
    )
    (net (code "69") (name "unconnected-(U3-PA8-Pad50)") (class "Default")
      (node (ref "U3") (pin "50") (pinfunction "PA8_50") (pintype "bidirectional"))
    )
    (net (code "70") (name "unconnected-(U3-PA9-Pad51)") (class "Default")
      (node (ref "U3") (pin "51") (pinfunction "PA9_51") (pintype "bidirectional"))
    )
    (net (code "71") (name "unconnected-(U3-PA15-Pad27)") (class "Default")
      (node (ref "U3") (pin "27") (pinfunction "PA15_27") (pintype "bidirectional"))
    )
    (net (code "72") (name "unconnected-(U3-PB0-Pad43)") (class "Default")
      (node (ref "U3") (pin "43") (pinfunction "PB0_43") (pintype "no_connect"))
    )
    (net (code "73") (name "unconnected-(U3-PB1-Pad44)") (class "Default")
      (node (ref "U3") (pin "44") (pinfunction "PB1_44") (pintype "no_connect"))
    )
    (net (code "74") (name "unconnected-(U3-PB2-Pad48)") (class "Default")
      (node (ref "U3") (pin "48") (pinfunction "PB2_48") (pintype "bidirectional"))
    )
    (net (code "75") (name "unconnected-(U3-PB3-Pad21)") (class "Default")
      (node (ref "U3") (pin "21") (pinfunction "PB3_21") (pintype "bidirectional"))
    )
    (net (code "76") (name "unconnected-(U3-PB4-Pad20)") (class "Default")
      (node (ref "U3") (pin "20") (pinfunction "PB4_20") (pintype "bidirectional"))
    )
    (net (code "77") (name "unconnected-(U3-PB5-Pad19)") (class "Default")
      (node (ref "U3") (pin "19") (pinfunction "PB5_19") (pintype "bidirectional"))
    )
    (net (code "78") (name "unconnected-(U3-PB8-Pad14)") (class "Default")
      (node (ref "U3") (pin "14") (pinfunction "PB8_14") (pintype "bidirectional"))
    )
    (net (code "79") (name "unconnected-(U3-PB9-Pad11)") (class "Default")
      (node (ref "U3") (pin "11") (pinfunction "PB9_11") (pintype "bidirectional"))
    )
    (net (code "80") (name "unconnected-(U3-PC1-Pad9)") (class "Default")
      (node (ref "U3") (pin "9") (pinfunction "PC1_9") (pintype "bidirectional"))
    )
    (net (code "81") (name "unconnected-(U3-PC3-Pad7)") (class "Default")
      (node (ref "U3") (pin "7") (pinfunction "PC3_7") (pintype "bidirectional"))
    )
    (net (code "82") (name "unconnected-(U3-PC4-Pad49)") (class "Default")
      (node (ref "U3") (pin "49") (pinfunction "PC4_49") (pintype "bidirectional"))
    )
    (net (code "83") (name "unconnected-(U3-PC7-Pad71)") (class "Default")
      (node (ref "U3") (pin "71") (pinfunction "PC7_71") (pintype "bidirectional"))
    )
    (net (code "84") (name "unconnected-(U3-PC9-Pad69)") (class "Default")
      (node (ref "U3") (pin "69") (pinfunction "PC9_69") (pintype "bidirectional"))
    )
    (net (code "85") (name "unconnected-(U3-PC10-Pad22)") (class "Default")
      (node (ref "U3") (pin "22") (pinfunction "PC10_22") (pintype "bidirectional"))
    )
    (net (code "86") (name "unconnected-(U3-PC11-Pad23)") (class "Default")
      (node (ref "U3") (pin "23") (pinfunction "PC11_23") (pintype "bidirectional"))
    )
    (net (code "87") (name "unconnected-(U3-PD0-Pad33)") (class "Default")
      (node (ref "U3") (pin "33") (pinfunction "PD0_33") (pintype "bidirectional"))
    )
    (net (code "88") (name "unconnected-(U3-PD2-Pad68)") (class "Default")
      (node (ref "U3") (pin "68") (pinfunction "PD2_68") (pintype "bidirectional"))
    )
    (net (code "89") (name "unconnected-(U3-PD3-Pad70)") (class "Default")
      (node (ref "U3") (pin "70") (pinfunction "PD3_70") (pintype "bidirectional"))
    )
    (net (code "90") (name "unconnected-(U3-PD5-Pad80)") (class "Default")
      (node (ref "U3") (pin "80") (pinfunction "PD5_80") (pintype "bidirectional"))
    )
    (net (code "91") (name "unconnected-(U3-PD6-Pad81)") (class "Default")
      (node (ref "U3") (pin "81") (pinfunction "PD6_81") (pintype "bidirectional"))
    )
    (net (code "92") (name "unconnected-(U3-PD7-Pad67)") (class "Default")
      (node (ref "U3") (pin "67") (pinfunction "PD7_67") (pintype "bidirectional"))
    )
    (net (code "93") (name "unconnected-(U3-PD8-Pad75)") (class "Default")
      (node (ref "U3") (pin "75") (pinfunction "PD8_75") (pintype "bidirectional"))
    )
    (net (code "94") (name "unconnected-(U3-PD9-Pad74)") (class "Default")
      (node (ref "U3") (pin "74") (pinfunction "PD9_74") (pintype "bidirectional"))
    )
    (net (code "95") (name "unconnected-(U3-PD10-Pad77)") (class "Default")
      (node (ref "U3") (pin "77") (pinfunction "PD10_77") (pintype "bidirectional"))
    )
    (net (code "96") (name "unconnected-(U3-PD11-Pad82)") (class "Default")
      (node (ref "U3") (pin "82") (pinfunction "PD11_82") (pintype "bidirectional"))
    )
    (net (code "97") (name "unconnected-(U3-PD12-Pad66)") (class "Default")
      (node (ref "U3") (pin "66") (pinfunction "PD12_66") (pintype "bidirectional"))
    )
    (net (code "98") (name "unconnected-(U3-PD13-Pad65)") (class "Default")
      (node (ref "U3") (pin "65") (pinfunction "PD13_65") (pintype "bidirectional"))
    )
    (net (code "99") (name "unconnected-(U3-PD14-Pad63)") (class "Default")
      (node (ref "U3") (pin "63") (pinfunction "PD14_63") (pintype "bidirectional"))
    )
    (net (code "100") (name "unconnected-(U3-PD15-Pad76)") (class "Default")
      (node (ref "U3") (pin "76") (pinfunction "PD15_76") (pintype "bidirectional"))
    )
    (net (code "101") (name "unconnected-(U3-PE0-Pad79)") (class "Default")
      (node (ref "U3") (pin "79") (pinfunction "PE0_79") (pintype "bidirectional"))
    )
    (net (code "102") (name "unconnected-(U3-PE1-Pad64)") (class "Default")
      (node (ref "U3") (pin "64") (pinfunction "PE1_64") (pintype "bidirectional"))
    )
    (net (code "103") (name "unconnected-(U3-PE2-Pad78)") (class "Default")
      (node (ref "U3") (pin "78") (pinfunction "PE2_78") (pintype "bidirectional"))
    )
    (net (code "104") (name "unconnected-(U3-PE4-Pad42)") (class "Default")
      (node (ref "U3") (pin "42") (pinfunction "PE4_42") (pintype "bidirectional"))
    )
    (net (code "105") (name "unconnected-(U3-PH0-Pad61)") (class "Default")
      (node (ref "U3") (pin "61") (pinfunction "PH0_61") (pintype "bidirectional"))
    )
    (net (code "106") (name "unconnected-(U3-PH1-Pad62)") (class "Default")
      (node (ref "U3") (pin "62") (pinfunction "PH1_62") (pintype "bidirectional"))
    )
    (net (code "107") (name "unconnected-(U4-K-Pad12)") (class "Default")
      (node (ref "U4") (pin "12") (pinfunction "K_12") (pintype "bidirectional"))
    )
    (net (code "108") (name "unconnected-(U4-L-Pad15)") (class "Default")
      (node (ref "U4") (pin "15") (pinfunction "L_15") (pintype "bidirectional"))
    )
    (net (code "109") (name "unconnected-(U4-NC_1-Pad13)") (class "Default")
      (node (ref "U4") (pin "13") (pinfunction "NC_1_13") (pintype "bidirectional"))
    )
    (net (code "110") (name "unconnected-(U4-NC_2-Pad16)") (class "Default")
      (node (ref "U4") (pin "16") (pinfunction "NC_2_16") (pintype "bidirectional"))
    )
    (net (code "111") (name "unconnected-(X1-Pad4)") (class "Default")
      (node (ref "X1") (pin "4") (pinfunction "4_4") (pintype "bidirectional"))
    )
    (net (code "112") (name "unconnected-(X2-DAT1-PadP8)") (class "Default")
      (node (ref "X2") (pin "P8") (pinfunction "DAT1_P8") (pintype "bidirectional"))
    )
    (net (code "113") (name "unconnected-(X2-DAT2-PadP1)") (class "Default")
      (node (ref "X2") (pin "P1") (pinfunction "DAT2_P1") (pintype "bidirectional"))
    )
  )
)
